# TempMeasure.net
KiCad netlist of a schematic drawn in Altium Designer
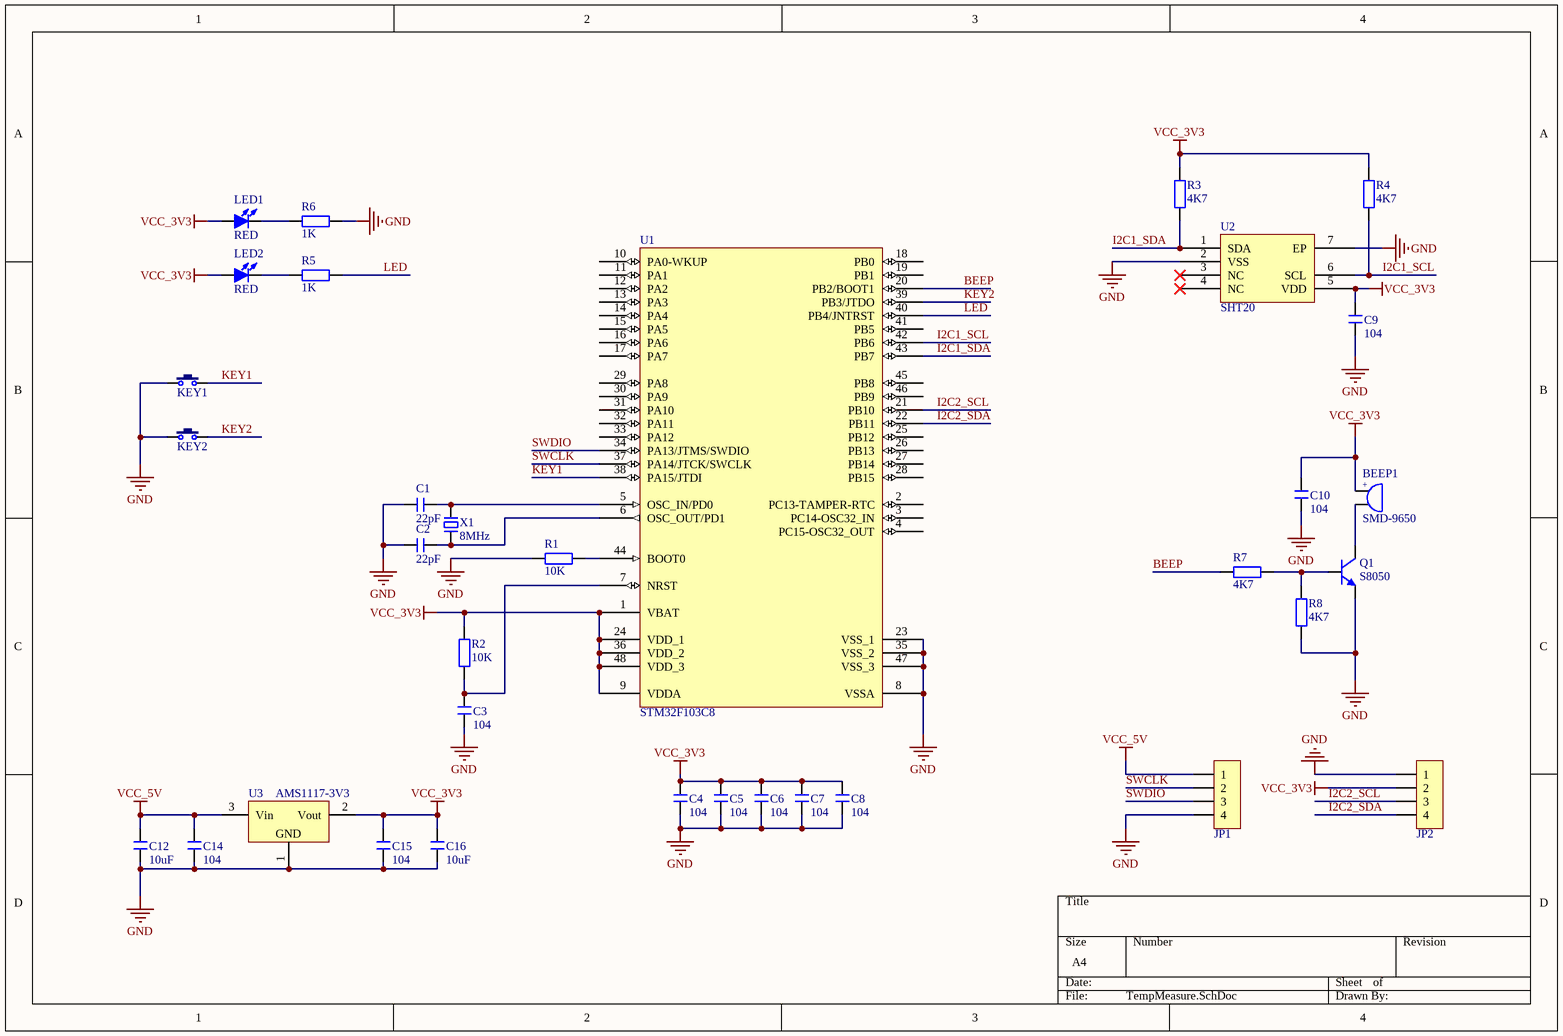
[diagram p0: TempMeasure.SchDoc]

(export (version "E")
  (design (tool "Eeschema 10.0.6"))
  (components
    (comp (ref "BEEP1")
      (value "SMD-9650")
      (footprint "BUZ-SMD-9650")
      (description "蜂鸣器")
      (fields (field (name "版权归属") "源创客"))
      (libsource (lib "STM32MP15x底板封装库V1.4") (part "BEEP"))
    )
    (comp (ref "C1")
      (value "22pF")
      (footprint "C 0805")
      (description "无极性贴片电容")
      (fields (field (name "版权归属") "源创客"))
      (libsource (lib "STM32MP15x底板封装库V1.4") (part "C"))
    )
    (comp (ref "C2")
      (value "22pF")
      (footprint "C 0805")
      (description "无极性贴片电容")
      (fields (field (name "版权归属") "源创客"))
      (libsource (lib "STM32MP15x底板封装库V1.4") (part "C"))
    )
    (comp (ref "C3")
      (value "104")
      (footprint "C 0805")
      (description "无极性贴片电容")
      (fields (field (name "版权归属") "源创客"))
      (libsource (lib "STM32MP15x底板封装库V1.4") (part "C"))
    )
    (comp (ref "C4")
      (value "104")
      (footprint "C 0805")
      (description "无极性贴片电容")
      (fields (field (name "版权归属") "源创客"))
      (libsource (lib "STM32MP15x底板封装库V1.4") (part "C"))
    )
    (comp (ref "C5")
      (value "104")
      (footprint "C 0805")
      (description "无极性贴片电容")
      (fields (field (name "版权归属") "源创客"))
      (libsource (lib "STM32MP15x底板封装库V1.4") (part "C"))
    )
    (comp (ref "C6")
      (value "104")
      (footprint "C 0805")
      (description "无极性贴片电容")
      (fields (field (name "版权归属") "源创客"))
      (libsource (lib "STM32MP15x底板封装库V1.4") (part "C"))
    )
    (comp (ref "C7")
      (value "104")
      (footprint "C 0805")
      (description "无极性贴片电容")
      (fields (field (name "版权归属") "源创客"))
      (libsource (lib "STM32MP15x底板封装库V1.4") (part "C"))
    )
    (comp (ref "C8")
      (value "104")
      (footprint "C 0805")
      (description "无极性贴片电容")
      (fields (field (name "版权归属") "源创客"))
      (libsource (lib "STM32MP15x底板封装库V1.4") (part "C"))
    )
    (comp (ref "C9")
      (value "104")
      (footprint "C 0805")
      (description "无极性贴片电容")
      (fields (field (name "版权归属") "源创客"))
      (libsource (lib "STM32MP15x底板封装库V1.4") (part "C"))
    )
    (comp (ref "C10")
      (value "104")
      (footprint "C 0805")
      (description "无极性贴片电容")
      (fields (field (name "版权归属") "源创客"))
      (libsource (lib "STM32MP15x底板封装库V1.4") (part "C"))
    )
    (comp (ref "C12")
      (value "10uF")
      (footprint "C 0805")
      (description "无极性贴片电容")
      (fields (field (name "版权归属") "源创客"))
      (libsource (lib "STM32MP15x底板封装库V1.4") (part "C"))
    )
    (comp (ref "C14")
      (value "104")
      (footprint "C 0805")
      (description "无极性贴片电容")
      (fields (field (name "版权归属") "源创客"))
      (libsource (lib "STM32MP15x底板封装库V1.4") (part "C"))
    )
    (comp (ref "C15")
      (value "104")
      (footprint "C 0805")
      (description "无极性贴片电容")
      (fields (field (name "版权归属") "源创客"))
      (libsource (lib "STM32MP15x底板封装库V1.4") (part "C"))
    )
    (comp (ref "C16")
      (value "10uF")
      (footprint "C 0805")
      (description "无极性贴片电容")
      (fields (field (name "版权归属") "源创客"))
      (libsource (lib "STM32MP15x底板封装库V1.4") (part "C"))
    )
    (comp (ref "JP1")
      (value "HDR-1X4")
      (footprint "XH2.54-LI-4P")
      (description "4P接插件")
      (fields (field (name "版权归属") "源创客"))
      (libsource (lib "4.5   - 接插件-脚距2.54") (part "Header 4"))
    )
    (comp (ref "JP2")
      (value "HDR-1X4")
      (footprint "HDR2.54-M-LI-4P")
      (description "4P接插件")
      (fields (field (name "版权归属") "源创客"))
      (libsource (lib "4.5   - 接插件-脚距2.54") (part "Header 4"))
    )
    (comp (ref "KEY1")
      (value "KEY")
      (footprint "ButtonTACT_3x4x2_180")
      (description "按键")
      (fields (field (name "版权归属") "源创客"))
      (libsource (lib "STM32MP15x底板封装库V1.4") (part "KEY"))
    )
    (comp (ref "KEY2")
      (value "KEY")
      (footprint "ButtonTACT_3x4x2_180")
      (description "按键")
      (fields (field (name "版权归属") "源创客"))
      (libsource (lib "STM32MP15x底板封装库V1.4") (part "KEY"))
    )
    (comp (ref "LED1")
      (value "RED")
      (footprint "LED 0805R")
      (description "贴片LED")
      (fields (field (name "版权归属") "源创客"))
      (libsource (lib "STM32MP15x底板封装库V1.4") (part "LED-SMD"))
    )
    (comp (ref "LED2")
      (value "RED")
      (footprint "LED 0805G")
      (description "贴片LED")
      (fields (field (name "版权归属") "源创客"))
      (libsource (lib "STM32MP15x底板封装库V1.4") (part "LED-SMD"))
    )
    (comp (ref "Q1")
      (value "S8050")
      (footprint "SOT23-3N")
      (description "高频放大-NPN型")
      (fields (field (name "版权归属") "源创客"))
      (libsource (lib "STM32MP15x底板封装库V1.4") (part "8050-SMD"))
    )
    (comp (ref "R1")
      (value "10K")
      (footprint "R 0805")
      (description "贴片电阻")
      (fields (field (name "版权归属") "源创客"))
      (libsource (lib "STM32MP15x底板封装库V1.4") (part "R"))
    )
    (comp (ref "R2")
      (value "10K")
      (footprint "R 0805")
      (description "贴片电阻")
      (fields (field (name "版权归属") "源创客"))
      (libsource (lib "STM32MP15x底板封装库V1.4") (part "R"))
    )
    (comp (ref "R3")
      (value "4K7")
      (footprint "R 0805")
      (description "贴片电阻")
      (fields (field (name "版权归属") "源创客"))
      (libsource (lib "STM32MP15x底板封装库V1.4") (part "R"))
    )
    (comp (ref "R4")
      (value "4K7")
      (footprint "R 0805")
      (description "贴片电阻")
      (fields (field (name "版权归属") "源创客"))
      (libsource (lib "STM32MP15x底板封装库V1.4") (part "R"))
    )
    (comp (ref "R5")
      (value "1K")
      (footprint "R 0805")
      (description "贴片电阻")
      (fields (field (name "版权归属") "源创客"))
      (libsource (lib "STM32MP15x底板封装库V1.4") (part "R"))
    )
    (comp (ref "R6")
      (value "1K")
      (footprint "R 0805")
      (description "贴片电阻")
      (fields (field (name "版权归属") "源创客"))
      (libsource (lib "STM32MP15x底板封装库V1.4") (part "R"))
    )
    (comp (ref "R7")
      (value "4K7")
      (footprint "R 0805")
      (description "贴片电阻")
      (fields (field (name "版权归属") "源创客"))
      (libsource (lib "STM32MP15x底板封装库V1.4") (part "R"))
    )
    (comp (ref "R8")
      (value "4K7")
      (footprint "R 0805")
      (description "贴片电阻")
      (fields (field (name "版权归属") "源创客"))
      (libsource (lib "STM32MP15x底板封装库V1.4") (part "R"))
    )
    (comp (ref "U1")
      (value "STM32F103C8")
      (footprint "LQFP48 7X7_N")
      (description "Flaah:64/RAM:20/IO:36")
      (fields (field (name "版权归属") "源创客"))
      (libsource (lib "2.1   - STM32系列单片机") (part "STM32F103C8"))
    )
    (comp (ref "U2") (value "SHT20") (footprint "DFN-6") (libsource (lib "SHT20") (part "SHT20")))
    (comp (ref "U3")
      (value "AMS1117-3V3")
      (footprint "SOT223_L")
      (description "三端稳压芯片")
      (fields (field (name "版权归属") "源创客"))
      (libsource (lib "1.3   - 电源类芯片") (part "AMS1117"))
    )
    (comp (ref "X1")
      (value "8MHz")
      (footprint "XTAL-49S SMD")
      (description "2脚无源晶振")
      (fields (field (name "版权归属") "源创客"))
      (libsource (lib "STM32MP15x底板封装库V1.4") (part "XTAL-2P"))
    )
  )
  (nets
    (net (code "1") (name "/BEEP") (class "Default")
      (node (ref "R7") (pin "1") (pinfunction "1_1") (pintype "passive"))
      (node (ref "U1") (pin "20") (pinfunction "PB2/BOOT1_20") (pintype "bidirectional"))
    )
    (net (code "2") (name "/I2C1_SCL") (class "Default")
      (node (ref "R4") (pin "1") (pinfunction "1_1") (pintype "passive"))
      (node (ref "U1") (pin "42") (pinfunction "PB6_42") (pintype "bidirectional"))
      (node (ref "U2") (pin "6") (pinfunction "SCL_6") (pintype "passive"))
    )
    (net (code "3") (name "/I2C1_SDA") (class "Default")
      (node (ref "R3") (pin "1") (pinfunction "1_1") (pintype "passive"))
      (node (ref "U1") (pin "43") (pinfunction "PB7_43") (pintype "bidirectional"))
      (node (ref "U2") (pin "1") (pinfunction "SDA_1") (pintype "passive"))
    )
    (net (code "4") (name "/I2C2_SCL") (class "Default")
      (node (ref "JP2") (pin "3") (pinfunction "3_3") (pintype "passive"))
      (node (ref "U1") (pin "21") (pinfunction "PB10_21") (pintype "bidirectional"))
    )
    (net (code "5") (name "/I2C2_SDA") (class "Default")
      (node (ref "JP2") (pin "4") (pinfunction "4_4") (pintype "passive"))
      (node (ref "U1") (pin "22") (pinfunction "PB11_22") (pintype "bidirectional"))
    )
    (net (code "6") (name "/KEY1") (class "Default")
      (node (ref "KEY1") (pin "2") (pinfunction "2_2") (pintype "passive"))
      (node (ref "U1") (pin "38") (pinfunction "PA15/JTDI_38") (pintype "bidirectional"))
    )
    (net (code "7") (name "/KEY2") (class "Default")
      (node (ref "KEY2") (pin "2") (pinfunction "2_2") (pintype "passive"))
      (node (ref "U1") (pin "39") (pinfunction "PB3/JTDO_39") (pintype "bidirectional"))
    )
    (net (code "8") (name "/LED") (class "Default")
      (node (ref "R5") (pin "2") (pinfunction "2_2") (pintype "passive"))
      (node (ref "U1") (pin "40") (pinfunction "PB4/JNTRST_40") (pintype "bidirectional"))
    )
    (net (code "9") (name "/SWCLK") (class "Default")
      (node (ref "JP1") (pin "2") (pinfunction "2_2") (pintype "passive"))
      (node (ref "U1") (pin "37") (pinfunction "PA14/JTCK/SWCLK_37") (pintype "bidirectional"))
    )
    (net (code "10") (name "/SWDIO") (class "Default")
      (node (ref "JP1") (pin "3") (pinfunction "3_3") (pintype "passive"))
      (node (ref "U1") (pin "34") (pinfunction "PA13/JTMS/SWDIO_34") (pintype "bidirectional"))
    )
    (net (code "11") (name "GND") (class "Default")
      (node (ref "C1") (pin "1") (pinfunction "1_1") (pintype "passive"))
      (node (ref "C10") (pin "1") (pinfunction "1_1") (pintype "passive"))
      (node (ref "C12") (pin "1") (pinfunction "1_1") (pintype "passive"))
      (node (ref "C14") (pin "2") (pinfunction "2_2") (pintype "passive"))
      (node (ref "C15") (pin "1") (pinfunction "1_1") (pintype "passive"))
      (node (ref "C16") (pin "1") (pinfunction "1_1") (pintype "passive"))
      (node (ref "C2") (pin "1") (pinfunction "1_1") (pintype "passive"))
      (node (ref "C3") (pin "1") (pinfunction "1_1") (pintype "passive"))
      (node (ref "C4") (pin "1") (pinfunction "1_1") (pintype "passive"))
      (node (ref "C5") (pin "1") (pinfunction "1_1") (pintype "passive"))
      (node (ref "C6") (pin "1") (pinfunction "1_1") (pintype "passive"))
      (node (ref "C7") (pin "1") (pinfunction "1_1") (pintype "passive"))
      (node (ref "C8") (pin "1") (pinfunction "1_1") (pintype "passive"))
      (node (ref "C9") (pin "1") (pinfunction "1_1") (pintype "passive"))
      (node (ref "JP1") (pin "4") (pinfunction "4_4") (pintype "passive"))
      (node (ref "JP2") (pin "1") (pinfunction "1_1") (pintype "passive"))
      (node (ref "KEY1") (pin "1") (pinfunction "1_1") (pintype "passive"))
      (node (ref "KEY2") (pin "1") (pinfunction "1_1") (pintype "passive"))
      (node (ref "Q1") (pin "2") (pinfunction "E_2") (pintype "passive"))
      (node (ref "R1") (pin "1") (pinfunction "1_1") (pintype "passive"))
      (node (ref "R6") (pin "2") (pinfunction "2_2") (pintype "passive"))
      (node (ref "R8") (pin "1") (pinfunction "1_1") (pintype "passive"))
      (node (ref "U1") (pin "23") (pinfunction "VSS_1_23") (pintype "power_in"))
      (node (ref "U1") (pin "35") (pinfunction "VSS_2_35") (pintype "power_in"))
      (node (ref "U1") (pin "47") (pinfunction "VSS_3_47") (pintype "power_in"))
      (node (ref "U1") (pin "8") (pinfunction "VSSA_8") (pintype "power_in"))
      (node (ref "U2") (pin "2") (pinfunction "VSS_2") (pintype "passive"))
      (node (ref "U2") (pin "7") (pinfunction "EP_7") (pintype "passive"))
      (node (ref "U3") (pin "1") (pinfunction "GND_1") (pintype "passive"))
    )
    (net (code "12") (name "Net-(LED1-K)") (class "Default")
      (node (ref "LED1") (pin "2") (pinfunction "K_2") (pintype "passive"))
      (node (ref "R6") (pin "1") (pinfunction "1_1") (pintype "passive"))
    )
    (net (code "13") (name "Net-(LED2-K)") (class "Default")
      (node (ref "LED2") (pin "2") (pinfunction "K_2") (pintype "passive"))
      (node (ref "R5") (pin "1") (pinfunction "1_1") (pintype "passive"))
    )
    (net (code "14") (name "Net-(Q1-B)") (class "Default")
      (node (ref "Q1") (pin "1") (pinfunction "B_1") (pintype "passive"))
      (node (ref "R7") (pin "2") (pinfunction "2_2") (pintype "passive"))
      (node (ref "R8") (pin "2") (pinfunction "2_2") (pintype "passive"))
    )
    (net (code "15") (name "Net-(Q1-C)") (class "Default")
      (node (ref "BEEP1") (pin "2") (pinfunction "2_2") (pintype "passive"))
      (node (ref "Q1") (pin "3") (pinfunction "C_3") (pintype "passive"))
    )
    (net (code "16") (name "Net-(U1-BOOT0)") (class "Default")
      (node (ref "R1") (pin "2") (pinfunction "2_2") (pintype "passive"))
      (node (ref "U1") (pin "44") (pinfunction "BOOT0_44") (pintype "input"))
    )
    (net (code "17") (name "Net-(U1-NRST)") (class "Default")
      (node (ref "C3") (pin "2") (pinfunction "2_2") (pintype "passive"))
      (node (ref "R2") (pin "1") (pinfunction "1_1") (pintype "passive"))
      (node (ref "U1") (pin "7") (pinfunction "NRST_7") (pintype "bidirectional"))
    )
    (net (code "18") (name "Net-(U1-OSC_IN{slash}PD0)") (class "Default")
      (node (ref "C1") (pin "2") (pinfunction "2_2") (pintype "passive"))
      (node (ref "U1") (pin "5") (pinfunction "OSC_IN/PD0_5") (pintype "input"))
      (node (ref "X1") (pin "2") (pinfunction "2_2") (pintype "passive"))
    )
    (net (code "19") (name "Net-(U1-OSC_OUT{slash}PD1)") (class "Default")
      (node (ref "C2") (pin "2") (pinfunction "2_2") (pintype "passive"))
      (node (ref "U1") (pin "6") (pinfunction "OSC_OUT/PD1_6") (pintype "output"))
      (node (ref "X1") (pin "1") (pinfunction "1_1") (pintype "passive"))
    )
    (net (code "20") (name "VCC_3V3") (class "Default")
      (node (ref "BEEP1") (pin "1") (pinfunction "1_1") (pintype "passive"))
      (node (ref "C10") (pin "2") (pinfunction "2_2") (pintype "passive"))
      (node (ref "C15") (pin "2") (pinfunction "2_2") (pintype "passive"))
      (node (ref "C16") (pin "2") (pinfunction "2_2") (pintype "passive"))
      (node (ref "C4") (pin "2") (pinfunction "2_2") (pintype "passive"))
      (node (ref "C5") (pin "2") (pinfunction "2_2") (pintype "passive"))
      (node (ref "C6") (pin "2") (pinfunction "2_2") (pintype "passive"))
      (node (ref "C7") (pin "2") (pinfunction "2_2") (pintype "passive"))
      (node (ref "C8") (pin "2") (pinfunction "2_2") (pintype "passive"))
      (node (ref "C9") (pin "2") (pinfunction "2_2") (pintype "passive"))
      (node (ref "JP2") (pin "2") (pinfunction "2_2") (pintype "passive"))
      (node (ref "LED1") (pin "1") (pinfunction "A_1") (pintype "passive"))
      (node (ref "LED2") (pin "1") (pinfunction "A_1") (pintype "passive"))
      (node (ref "R2") (pin "2") (pinfunction "2_2") (pintype "passive"))
      (node (ref "R3") (pin "2") (pinfunction "2_2") (pintype "passive"))
      (node (ref "R4") (pin "2") (pinfunction "2_2") (pintype "passive"))
      (node (ref "U1") (pin "1") (pinfunction "VBAT_1") (pintype "power_in"))
      (node (ref "U1") (pin "24") (pinfunction "VDD_1_24") (pintype "power_in"))
      (node (ref "U1") (pin "36") (pinfunction "VDD_2_36") (pintype "power_in"))
      (node (ref "U1") (pin "48") (pinfunction "VDD_3_48") (pintype "power_in"))
      (node (ref "U1") (pin "9") (pinfunction "VDDA_9") (pintype "power_in"))
      (node (ref "U2") (pin "5") (pinfunction "VDD_5") (pintype "passive"))
      (node (ref "U3") (pin "2") (pinfunction "Vout_2") (pintype "passive"))
    )
    (net (code "21") (name "VCC_5V") (class "Default")
      (node (ref "C12") (pin "2") (pinfunction "2_2") (pintype "passive"))
      (node (ref "C14") (pin "1") (pinfunction "1_1") (pintype "passive"))
      (node (ref "JP1") (pin "1") (pinfunction "1_1") (pintype "passive"))
      (node (ref "U3") (pin "3") (pinfunction "Vin_3") (pintype "passive"))
    )
    (net (code "22") (name "unconnected-(U1-PA0-WKUP-Pad10)") (class "Default")
      (node (ref "U1") (pin "10") (pinfunction "PA0-WKUP_10") (pintype "bidirectional"))
    )
    (net (code "23") (name "unconnected-(U1-PA1-Pad11)") (class "Default")
      (node (ref "U1") (pin "11") (pinfunction "PA1_11") (pintype "bidirectional"))
    )
    (net (code "24") (name "unconnected-(U1-PA2-Pad12)") (class "Default")
      (node (ref "U1") (pin "12") (pinfunction "PA2_12") (pintype "bidirectional"))
    )
    (net (code "25") (name "unconnected-(U1-PA3-Pad13)") (class "Default")
      (node (ref "U1") (pin "13") (pinfunction "PA3_13") (pintype "bidirectional"))
    )
    (net (code "26") (name "unconnected-(U1-PA4-Pad14)") (class "Default")
      (node (ref "U1") (pin "14") (pinfunction "PA4_14") (pintype "bidirectional"))
    )
    (net (code "27") (name "unconnected-(U1-PA5-Pad15)") (class "Default")
      (node (ref "U1") (pin "15") (pinfunction "PA5_15") (pintype "bidirectional"))
    )
    (net (code "28") (name "unconnected-(U1-PA6-Pad16)") (class "Default")
      (node (ref "U1") (pin "16") (pinfunction "PA6_16") (pintype "bidirectional"))
    )
    (net (code "29") (name "unconnected-(U1-PA7-Pad17)") (class "Default")
      (node (ref "U1") (pin "17") (pinfunction "PA7_17") (pintype "bidirectional"))
    )
    (net (code "30") (name "unconnected-(U1-PA8-Pad29)") (class "Default")
      (node (ref "U1") (pin "29") (pinfunction "PA8_29") (pintype "bidirectional"))
    )
    (net (code "31") (name "unconnected-(U1-PA9-Pad30)") (class "Default")
      (node (ref "U1") (pin "30") (pinfunction "PA9_30") (pintype "bidirectional"))
    )
    (net (code "32") (name "unconnected-(U1-PA10-Pad31)") (class "Default")
      (node (ref "U1") (pin "31") (pinfunction "PA10_31") (pintype "bidirectional"))
    )
    (net (code "33") (name "unconnected-(U1-PA11-Pad32)") (class "Default")
      (node (ref "U1") (pin "32") (pinfunction "PA11_32") (pintype "bidirectional"))
    )
    (net (code "34") (name "unconnected-(U1-PA12-Pad33)") (class "Default")
      (node (ref "U1") (pin "33") (pinfunction "PA12_33") (pintype "bidirectional"))
    )
    (net (code "35") (name "unconnected-(U1-PB0-Pad18)") (class "Default")
      (node (ref "U1") (pin "18") (pinfunction "PB0_18") (pintype "bidirectional"))
    )
    (net (code "36") (name "unconnected-(U1-PB1-Pad19)") (class "Default")
      (node (ref "U1") (pin "19") (pinfunction "PB1_19") (pintype "bidirectional"))
    )
    (net (code "37") (name "unconnected-(U1-PB5-Pad41)") (class "Default")
      (node (ref "U1") (pin "41") (pinfunction "PB5_41") (pintype "bidirectional"))
    )
    (net (code "38") (name "unconnected-(U1-PB8-Pad45)") (class "Default")
      (node (ref "U1") (pin "45") (pinfunction "PB8_45") (pintype "bidirectional"))
    )
    (net (code "39") (name "unconnected-(U1-PB9-Pad46)") (class "Default")
      (node (ref "U1") (pin "46") (pinfunction "PB9_46") (pintype "bidirectional"))
    )
    (net (code "40") (name "unconnected-(U1-PB12-Pad25)") (class "Default")
      (node (ref "U1") (pin "25") (pinfunction "PB12_25") (pintype "bidirectional"))
    )
    (net (code "41") (name "unconnected-(U1-PB13-Pad26)") (class "Default")
      (node (ref "U1") (pin "26") (pinfunction "PB13_26") (pintype "bidirectional"))
    )
    (net (code "42") (name "unconnected-(U1-PB14-Pad27)") (class "Default")
      (node (ref "U1") (pin "27") (pinfunction "PB14_27") (pintype "bidirectional"))
    )
    (net (code "43") (name "unconnected-(U1-PB15-Pad28)") (class "Default")
      (node (ref "U1") (pin "28") (pinfunction "PB15_28") (pintype "bidirectional"))
    )
    (net (code "44") (name "unconnected-(U1-PC13-TAMPER-RTC-Pad2)") (class "Default")
      (node (ref "U1") (pin "2") (pinfunction "PC13-TAMPER-RTC_2") (pintype "bidirectional"))
    )
    (net (code "45") (name "unconnected-(U1-PC14-OSC32_IN-Pad3)") (class "Default")
      (node (ref "U1") (pin "3") (pinfunction "PC14-OSC32_IN_3") (pintype "bidirectional"))
    )
    (net (code "46") (name "unconnected-(U1-PC15-OSC32_OUT-Pad4)") (class "Default")
      (node (ref "U1") (pin "4") (pinfunction "PC15-OSC32_OUT_4") (pintype "bidirectional"))
    )
    (net (code "47") (name "unconnected-(U2-NC-Pad3)") (class "Default")
      (node (ref "U2") (pin "3") (pinfunction "NC_3") (pintype "passive+no_connect"))
    )
    (net (code "48") (name "unconnected-(U2-NC-Pad4)") (class "Default")
      (node (ref "U2") (pin "4") (pinfunction "NC_4") (pintype "passive+no_connect"))
    )
  )
)
